# Connectors.net
KiCad netlist of a schematic drawn in Altium Designer
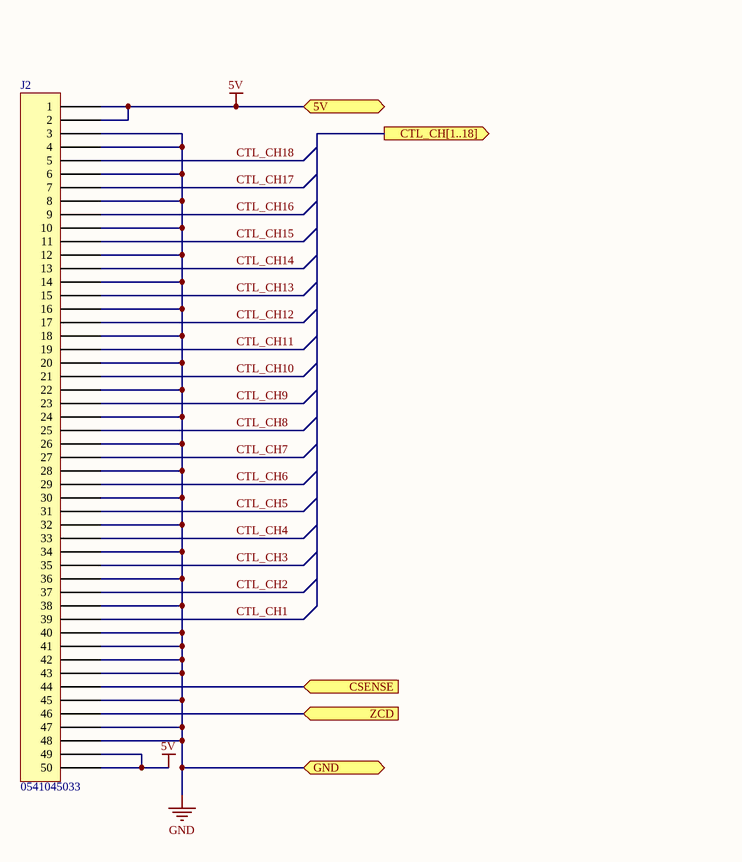
[diagram p0: Connectors.SchDoc]

(export (version "E")
  (design (tool "Eeschema 10.0.6"))
  (components
    (comp (ref "J2")
      (value "0541045033")
      (footprint "MOLEX 0541045033")
      (description "CONN FFC TOP 50POS 0.50MM R/A")
      (fields (field (name "MANUFACTURER") "Molex"))
      (libsource (lib "altiumlibrary.com") (part "50 Pin"))
    )
  )
  (nets
    (net (code "1") (name "/CSENSE") (class "Default")
      (node (ref "J2") (pin "44") (pinfunction "44_44") (pintype "passive"))
    )
    (net (code "2") (name "/CTL_CH1") (class "Default")
      (node (ref "J2") (pin "39") (pinfunction "39_39") (pintype "passive"))
    )
    (net (code "3") (name "/CTL_CH2") (class "Default")
      (node (ref "J2") (pin "37") (pinfunction "37_37") (pintype "passive"))
    )
    (net (code "4") (name "/CTL_CH3") (class "Default")
      (node (ref "J2") (pin "35") (pinfunction "35_35") (pintype "passive"))
    )
    (net (code "5") (name "/CTL_CH4") (class "Default")
      (node (ref "J2") (pin "33") (pinfunction "33_33") (pintype "passive"))
    )
    (net (code "6") (name "/CTL_CH5") (class "Default")
      (node (ref "J2") (pin "31") (pinfunction "31_31") (pintype "passive"))
    )
    (net (code "7") (name "/CTL_CH6") (class "Default")
      (node (ref "J2") (pin "29") (pinfunction "29_29") (pintype "passive"))
    )
    (net (code "8") (name "/CTL_CH7") (class "Default")
      (node (ref "J2") (pin "27") (pinfunction "27_27") (pintype "passive"))
    )
    (net (code "9") (name "/CTL_CH8") (class "Default")
      (node (ref "J2") (pin "25") (pinfunction "25_25") (pintype "passive"))
    )
    (net (code "10") (name "/CTL_CH9") (class "Default")
      (node (ref "J2") (pin "23") (pinfunction "23_23") (pintype "passive"))
    )
    (net (code "11") (name "/CTL_CH10") (class "Default")
      (node (ref "J2") (pin "21") (pinfunction "21_21") (pintype "passive"))
    )
    (net (code "12") (name "/CTL_CH11") (class "Default")
      (node (ref "J2") (pin "19") (pinfunction "19_19") (pintype "passive"))
    )
    (net (code "13") (name "/CTL_CH12") (class "Default")
      (node (ref "J2") (pin "17") (pinfunction "17_17") (pintype "passive"))
    )
    (net (code "14") (name "/CTL_CH13") (class "Default")
      (node (ref "J2") (pin "15") (pinfunction "15_15") (pintype "passive"))
    )
    (net (code "15") (name "/CTL_CH14") (class "Default")
      (node (ref "J2") (pin "13") (pinfunction "13_13") (pintype "passive"))
    )
    (net (code "16") (name "/CTL_CH15") (class "Default")
      (node (ref "J2") (pin "11") (pinfunction "11_11") (pintype "passive"))
    )
    (net (code "17") (name "/CTL_CH16") (class "Default")
      (node (ref "J2") (pin "9") (pinfunction "9_9") (pintype "passive"))
    )
    (net (code "18") (name "/CTL_CH17") (class "Default")
      (node (ref "J2") (pin "7") (pinfunction "7_7") (pintype "passive"))
    )
    (net (code "19") (name "/CTL_CH18") (class "Default")
      (node (ref "J2") (pin "5") (pinfunction "5_5") (pintype "passive"))
    )
    (net (code "21") (name "/ZCD") (class "Default")
      (node (ref "J2") (pin "46") (pinfunction "46_46") (pintype "passive"))
    )
    (net (code "22") (name "5V") (class "Default")
      (node (ref "J2") (pin "1") (pinfunction "1_1") (pintype "passive"))
      (node (ref "J2") (pin "2") (pinfunction "2_2") (pintype "passive"))
      (node (ref "J2") (pin "49") (pinfunction "49_49") (pintype "passive"))
      (node (ref "J2") (pin "50") (pinfunction "50_50") (pintype "passive"))
    )
    (net (code "23") (name "GND") (class "Default")
      (node (ref "J2") (pin "10") (pinfunction "10_10") (pintype "passive"))
      (node (ref "J2") (pin "12") (pinfunction "12_12") (pintype "passive"))
      (node (ref "J2") (pin "14") (pinfunction "14_14") (pintype "passive"))
      (node (ref "J2") (pin "16") (pinfunction "16_16") (pintype "passive"))
      (node (ref "J2") (pin "18") (pinfunction "18_18") (pintype "passive"))
      (node (ref "J2") (pin "20") (pinfunction "20_20") (pintype "passive"))
      (node (ref "J2") (pin "22") (pinfunction "22_22") (pintype "passive"))
      (node (ref "J2") (pin "24") (pinfunction "24_24") (pintype "passive"))
      (node (ref "J2") (pin "26") (pinfunction "26_26") (pintype "passive"))
      (node (ref "J2") (pin "28") (pinfunction "28_28") (pintype "passive"))
      (node (ref "J2") (pin "3") (pinfunction "3_3") (pintype "passive"))
      (node (ref "J2") (pin "30") (pinfunction "30_30") (pintype "passive"))
      (node (ref "J2") (pin "32") (pinfunction "32_32") (pintype "passive"))
      (node (ref "J2") (pin "34") (pinfunction "34_34") (pintype "passive"))
      (node (ref "J2") (pin "36") (pinfunction "36_36") (pintype "passive"))
      (node (ref "J2") (pin "38") (pinfunction "38_38") (pintype "passive"))
      (node (ref "J2") (pin "4") (pinfunction "4_4") (pintype "passive"))
      (node (ref "J2") (pin "40") (pinfunction "40_40") (pintype "passive"))
      (node (ref "J2") (pin "41") (pinfunction "41_41") (pintype "passive"))
      (node (ref "J2") (pin "42") (pinfunction "42_42") (pintype "passive"))
      (node (ref "J2") (pin "43") (pinfunction "43_43") (pintype "passive"))
      (node (ref "J2") (pin "45") (pinfunction "45_45") (pintype "passive"))
      (node (ref "J2") (pin "47") (pinfunction "47_47") (pintype "passive"))
      (node (ref "J2") (pin "48") (pinfunction "48_48") (pintype "passive"))
      (node (ref "J2") (pin "6") (pinfunction "6_6") (pintype "passive"))
      (node (ref "J2") (pin "8") (pinfunction "8_8") (pintype "passive"))
    )
  )
)
